# CanNode.net
KiCad netlist of a schematic drawn in Altium Designer
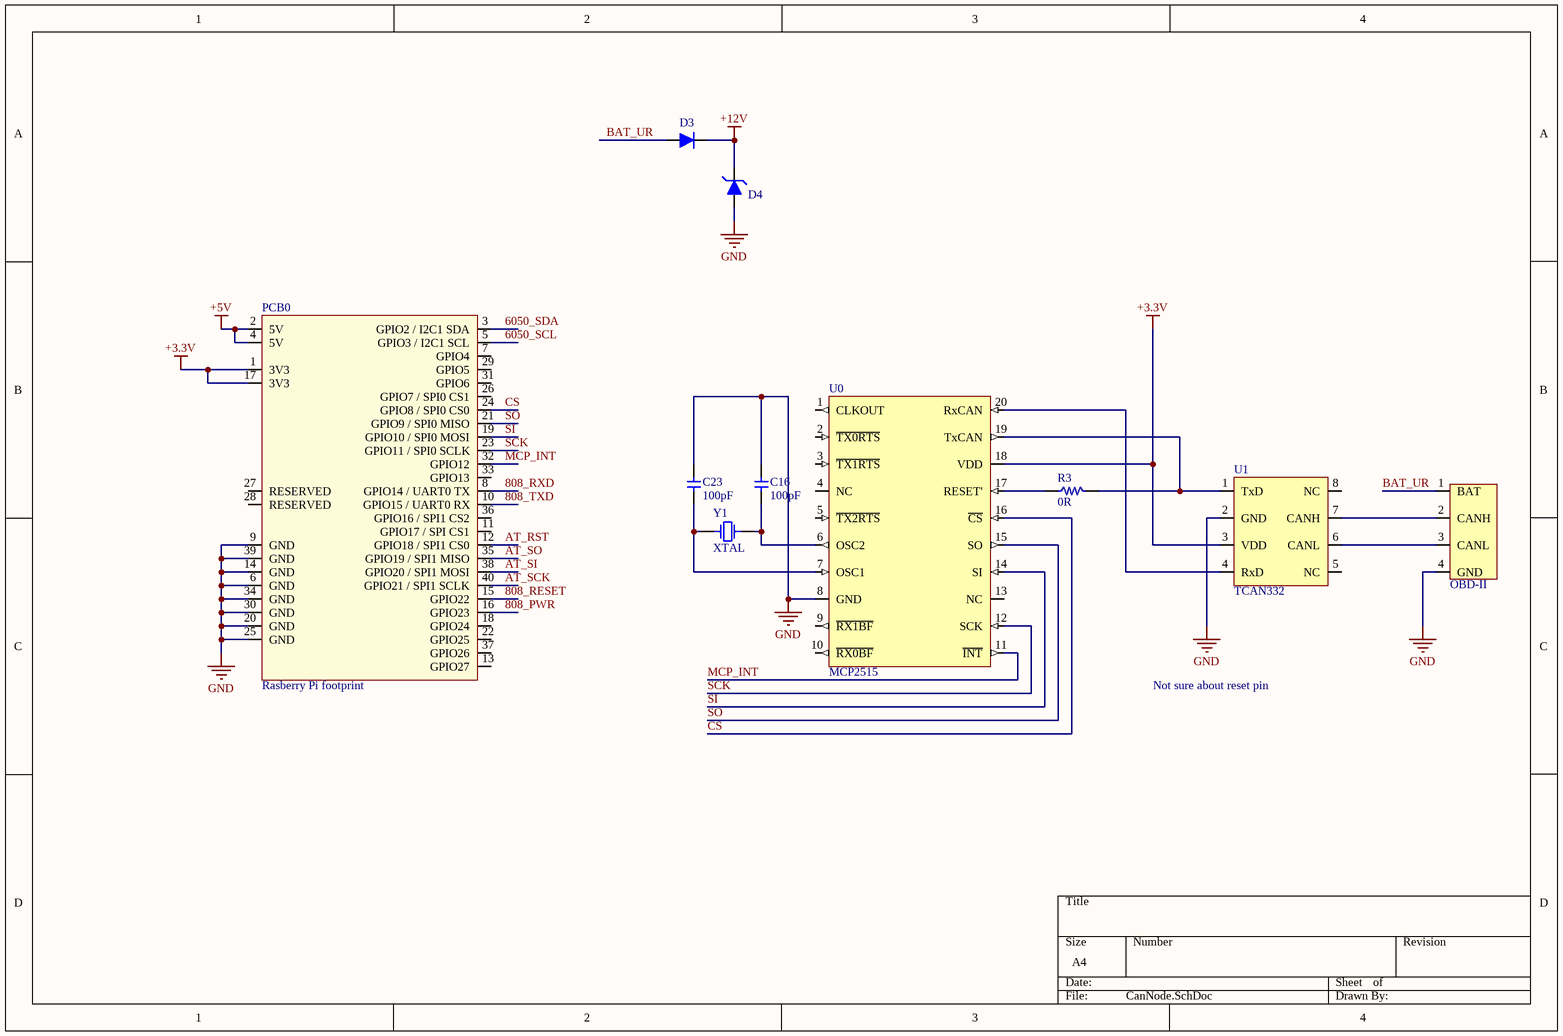
[diagram p0: CanNode.SchDoc]

(export (version "E")
  (design (tool "Eeschema 10.0.6"))
  (components
    (comp (ref "C16")
      (value "100pF")
      (footprint "0805")
      (description "Generic capacitor")
      (fields (field (name "Comment") "Generic Capacitor"))
      (libsource (lib "PowerCircuit") (part "Capacitor"))
    )
    (comp (ref "C23")
      (value "100pF")
      (footprint "0805")
      (description "Generic capacitor")
      (fields (field (name "Comment") "Generic Capacitor"))
      (libsource (lib "PowerCircuit") (part "Capacitor"))
    )
    (comp (ref "D3")
      (value "RSX301L-30TE25")
      (footprint "SMA_diode")
      (description "DIODE SCHOTTKY 30V 3A")
      (libsource (lib "PowerCircuit") (part "RSX301L-30TE25"))
    )
    (comp (ref "D4")
      (value "TVS Diode")
      (footprint "TVS Diode 15")
      (description "TVS DIODE 15VWM 24VC DO214AA")
      (fields
        (field (name "MANUFACTURER") "Vishay Semiconductor Diodes Division")
        (field (name "MANUFACTURER PART NUMBER") "SMBJ15D-M3/H")
      )
      (libsource (lib "CanNode") (part "SMBJ15D-M3/H"))
    )
    (comp (ref "OBD-II") (value "OBD-II") (footprint "OBD_II") (libsource (lib "CanNode") (part "OBD-II")))
    (comp (ref "PCB0")
      (value "Rasberry Pi footprint")
      (footprint "Rasberry PI")
      (libsource (lib "CanNode") (part "Rasberry Pi"))
    )
    (comp (ref "R3")
      (value "0R")
      (footprint "0805")
      (description "Generic Resistor")
      (fields (field (name "Comment") "Resistor"))
      (libsource (lib "PowerCircuit") (part "Resistor"))
    )
    (comp (ref "U0")
      (value "MCP2515")
      (footprint "MCP2515")
      (description "IC CAN CTLR W/SPI 2.0B 20-QFN")
      (fields
        (field (name "DIGI-KEY PART NUMBER") "MCP2515T-I/MLCT-ND")
        (field (name "NOTES") "Not sure about reset pin")
      )
      (libsource (lib "CanNode") (part "MCP2515"))
    )
    (comp (ref "U1")
      (value "TCAN332")
      (footprint "SOIC-8")
      (description "IC TXRX CAN 8SOIC")
      (fields (field (name "DIGI-KEY PART NUMBER") "296-43711-1-ND"))
      (libsource (lib "CanNode") (part "TCAN332"))
    )
    (comp (ref "Y1")
      (value "XTAL")
      (footprint "XTAL-16.000")
      (description "XTAL16.0000MHZ 18PF SMD")
      (fields
        (field (name "MANUFACTURER") "Abracon LLC")
        (field (name "MANUFACTURER PART NUMBER") "ABM7-16.000MHZ-D2Y-T")
      )
      (libsource (lib "CanNode") (part "XTAL-16.000"))
    )
  )
  (nets
    (net (code "1") (name "+3.3V") (class "Default")
      (node (ref "PCB0") (pin "1") (pinfunction "3V3_1") (pintype "passive"))
      (node (ref "PCB0") (pin "17") (pinfunction "3V3_17") (pintype "passive"))
      (node (ref "U0") (pin "18") (pinfunction "VDD_18") (pintype "power_in"))
      (node (ref "U1") (pin "3") (pinfunction "VDD_3") (pintype "passive"))
    )
    (net (code "2") (name "+5V") (class "Default")
      (node (ref "PCB0") (pin "2") (pinfunction "5V_2") (pintype "passive"))
      (node (ref "PCB0") (pin "4") (pinfunction "5V_4") (pintype "passive"))
    )
    (net (code "3") (name "+12V") (class "Default")
      (node (ref "D3") (pin "2") (pinfunction "2_2") (pintype "passive"))
      (node (ref "D4") (pin "2") (pinfunction "2_2") (pintype "passive"))
    )
    (net (code "4") (name "/808_PWR") (class "Default")
      (node (ref "PCB0") (pin "16") (pinfunction "GPIO23_16") (pintype "passive"))
    )
    (net (code "5") (name "/808_RESET") (class "Default")
      (node (ref "PCB0") (pin "15") (pinfunction "GPIO22_15") (pintype "passive"))
    )
    (net (code "6") (name "/808_RXD") (class "Default")
      (node (ref "PCB0") (pin "8") (pinfunction "GPIO14_/_UART0_TX_8") (pintype "passive"))
    )
    (net (code "7") (name "/808_TXD") (class "Default")
      (node (ref "PCB0") (pin "10") (pinfunction "GPIO15_/_UART0_RX_10") (pintype "passive"))
    )
    (net (code "8") (name "/6050_SCL") (class "Default")
      (node (ref "PCB0") (pin "5") (pinfunction "GPIO3_/_I2C1_SCL_5") (pintype "passive"))
    )
    (net (code "9") (name "/6050_SDA") (class "Default")
      (node (ref "PCB0") (pin "3") (pinfunction "GPIO2_/_I2C1_SDA_3") (pintype "passive"))
    )
    (net (code "10") (name "/AT_RST") (class "Default")
      (node (ref "PCB0") (pin "12") (pinfunction "GPIO18_/_SPI1_CS0_12") (pintype "passive"))
    )
    (net (code "11") (name "/AT_SCK") (class "Default")
      (node (ref "PCB0") (pin "40") (pinfunction "GPIO21_/_SPI1_SCLK_40") (pintype "passive"))
    )
    (net (code "12") (name "/AT_SI") (class "Default")
      (node (ref "PCB0") (pin "38") (pinfunction "GPIO20_/_SPI1_MOSI_38") (pintype "passive"))
    )
    (net (code "13") (name "/AT_SO") (class "Default")
      (node (ref "PCB0") (pin "35") (pinfunction "GPIO19_/_SPI1_MISO_35") (pintype "passive"))
    )
    (net (code "14") (name "/BAT_UR") (class "Default")
      (node (ref "D3") (pin "1") (pinfunction "1_1") (pintype "passive"))
      (node (ref "OBD-II") (pin "1") (pinfunction "BAT_1") (pintype "passive"))
    )
    (net (code "15") (name "/CS") (class "Default")
      (node (ref "PCB0") (pin "24") (pinfunction "GPIO8_/_SPI0_CS0_24") (pintype "passive"))
      (node (ref "U0") (pin "16") (pinfunction "~{CS}_16") (pintype "input"))
    )
    (net (code "16") (name "/MCP_INT") (class "Default")
      (node (ref "PCB0") (pin "32") (pinfunction "GPIO12_32") (pintype "passive"))
      (node (ref "U0") (pin "11") (pinfunction "~{INT}_11") (pintype "output"))
    )
    (net (code "17") (name "/SCK") (class "Default")
      (node (ref "PCB0") (pin "23") (pinfunction "GPIO11_/_SPI0_SCLK_23") (pintype "passive"))
      (node (ref "U0") (pin "12") (pinfunction "SCK_12") (pintype "input"))
    )
    (net (code "18") (name "/SI") (class "Default")
      (node (ref "PCB0") (pin "19") (pinfunction "GPIO10_/_SPI0_MOSI_19") (pintype "passive"))
      (node (ref "U0") (pin "14") (pinfunction "SI_14") (pintype "input"))
    )
    (net (code "19") (name "/SO") (class "Default")
      (node (ref "PCB0") (pin "21") (pinfunction "GPIO9_/_SPI0_MISO_21") (pintype "passive"))
      (node (ref "U0") (pin "15") (pinfunction "SO_15") (pintype "output"))
    )
    (net (code "20") (name "GND") (class "Default")
      (node (ref "C16") (pin "2") (pinfunction "2_2") (pintype "passive"))
      (node (ref "C23") (pin "2") (pinfunction "2_2") (pintype "passive"))
      (node (ref "D4") (pin "1") (pinfunction "1_1") (pintype "passive"))
      (node (ref "OBD-II") (pin "4") (pinfunction "GND_4") (pintype "passive"))
      (node (ref "PCB0") (pin "14") (pinfunction "GND_14") (pintype "passive"))
      (node (ref "PCB0") (pin "20") (pinfunction "GND_20") (pintype "passive"))
      (node (ref "PCB0") (pin "25") (pinfunction "GND_25") (pintype "passive"))
      (node (ref "PCB0") (pin "30") (pinfunction "GND_30") (pintype "passive"))
      (node (ref "PCB0") (pin "34") (pinfunction "GND_34") (pintype "passive"))
      (node (ref "PCB0") (pin "39") (pinfunction "GND_39") (pintype "passive"))
      (node (ref "PCB0") (pin "6") (pinfunction "GND_6") (pintype "passive"))
      (node (ref "PCB0") (pin "9") (pinfunction "GND_9") (pintype "passive"))
      (node (ref "U0") (pin "8") (pinfunction "GND_8") (pintype "power_in"))
      (node (ref "U1") (pin "2") (pinfunction "GND_2") (pintype "passive"))
    )
    (net (code "21") (name "Net-(OBD-II-CANH)") (class "Default")
      (node (ref "OBD-II") (pin "2") (pinfunction "CANH_2") (pintype "passive"))
      (node (ref "U1") (pin "7") (pinfunction "CANH_7") (pintype "passive"))
    )
    (net (code "22") (name "Net-(OBD-II-CANL)") (class "Default")
      (node (ref "OBD-II") (pin "3") (pinfunction "CANL_3") (pintype "passive"))
      (node (ref "U1") (pin "6") (pinfunction "CANL_6") (pintype "passive"))
    )
    (net (code "23") (name "Net-(U0-OSC1)") (class "Default")
      (node (ref "C23") (pin "1") (pinfunction "1_1") (pintype "passive"))
      (node (ref "U0") (pin "7") (pinfunction "OSC1_7") (pintype "input"))
      (node (ref "Y1") (pin "0") (pinfunction "0_0") (pintype "passive"))
    )
    (net (code "24") (name "Net-(U0-OSC2)") (class "Default")
      (node (ref "C16") (pin "1") (pinfunction "1_1") (pintype "passive"))
      (node (ref "U0") (pin "6") (pinfunction "OSC2_6") (pintype "output"))
      (node (ref "Y1") (pin "1") (pinfunction "1_1") (pintype "passive"))
    )
    (net (code "25") (name "Net-(U0-RESET')") (class "Default")
      (node (ref "R3") (pin "1") (pinfunction "1_1") (pintype "passive"))
      (node (ref "U0") (pin "17") (pinfunction "RESET'_17") (pintype "input"))
    )
    (net (code "26") (name "Net-(U0-RxCAN)") (class "Default")
      (node (ref "U0") (pin "20") (pinfunction "RxCAN_20") (pintype "input"))
      (node (ref "U1") (pin "4") (pinfunction "RxD_4") (pintype "passive"))
    )
    (net (code "27") (name "Net-(U0-TxCAN)") (class "Default")
      (node (ref "R3") (pin "2") (pinfunction "2_2") (pintype "passive"))
      (node (ref "U0") (pin "19") (pinfunction "TxCAN_19") (pintype "output"))
      (node (ref "U1") (pin "1") (pinfunction "TxD_1") (pintype "passive"))
    )
    (net (code "28") (name "unconnected-(PCB0-GPIO4-Pad7)") (class "Default")
      (node (ref "PCB0") (pin "7") (pinfunction "GPIO4_7") (pintype "passive"))
    )
    (net (code "29") (name "unconnected-(PCB0-GPIO5-Pad29)") (class "Default")
      (node (ref "PCB0") (pin "29") (pinfunction "GPIO5_29") (pintype "passive"))
    )
    (net (code "30") (name "unconnected-(PCB0-GPIO6-Pad31)") (class "Default")
      (node (ref "PCB0") (pin "31") (pinfunction "GPIO6_31") (pintype "passive"))
    )
    (net (code "31") (name "unconnected-(PCB0-GPIO7_{slash}_SPI0_CS1-Pad26)") (class "Default")
      (node (ref "PCB0") (pin "26") (pinfunction "GPIO7_/_SPI0_CS1_26") (pintype "passive"))
    )
    (net (code "32") (name "unconnected-(PCB0-GPIO13-Pad33)") (class "Default")
      (node (ref "PCB0") (pin "33") (pinfunction "GPIO13_33") (pintype "passive"))
    )
    (net (code "33") (name "unconnected-(PCB0-GPIO16_{slash}_SPI1_CS2-Pad36)") (class "Default")
      (node (ref "PCB0") (pin "36") (pinfunction "GPIO16_/_SPI1_CS2_36") (pintype "passive"))
    )
    (net (code "34") (name "unconnected-(PCB0-GPIO17_{slash}_SPI_CS1-Pad11)") (class "Default")
      (node (ref "PCB0") (pin "11") (pinfunction "GPIO17_/_SPI_CS1_11") (pintype "passive"))
    )
    (net (code "35") (name "unconnected-(PCB0-GPIO24-Pad18)") (class "Default")
      (node (ref "PCB0") (pin "18") (pinfunction "GPIO24_18") (pintype "passive"))
    )
    (net (code "36") (name "unconnected-(PCB0-GPIO25-Pad22)") (class "Default")
      (node (ref "PCB0") (pin "22") (pinfunction "GPIO25_22") (pintype "passive"))
    )
    (net (code "37") (name "unconnected-(PCB0-GPIO26-Pad37)") (class "Default")
      (node (ref "PCB0") (pin "37") (pinfunction "GPIO26_37") (pintype "passive"))
    )
    (net (code "38") (name "unconnected-(PCB0-GPIO27-Pad13)") (class "Default")
      (node (ref "PCB0") (pin "13") (pinfunction "GPIO27_13") (pintype "passive"))
    )
    (net (code "39") (name "unconnected-(PCB0-RESERVED-Pad27)") (class "Default")
      (node (ref "PCB0") (pin "27") (pinfunction "RESERVED_27") (pintype "passive"))
    )
    (net (code "40") (name "unconnected-(PCB0-RESERVED-Pad28)") (class "Default")
      (node (ref "PCB0") (pin "28") (pinfunction "RESERVED_28") (pintype "passive"))
    )
    (net (code "41") (name "unconnected-(U0-CLKOUT-Pad1)") (class "Default")
      (node (ref "U0") (pin "1") (pinfunction "CLKOUT_1") (pintype "output"))
    )
    (net (code "42") (name "unconnected-(U0-NC-Pad4)") (class "Default")
      (node (ref "U0") (pin "4") (pinfunction "NC_4") (pintype "passive"))
    )
    (net (code "43") (name "unconnected-(U0-NC-Pad13)") (class "Default")
      (node (ref "U0") (pin "13") (pinfunction "NC_13") (pintype "passive"))
    )
    (net (code "44") (name "unconnected-(U0-~{RX0BF}-Pad10)") (class "Default")
      (node (ref "U0") (pin "10") (pinfunction "~{RX0BF}_10") (pintype "output"))
    )
    (net (code "45") (name "unconnected-(U0-~{RX1BF}-Pad9)") (class "Default")
      (node (ref "U0") (pin "9") (pinfunction "~{RX1BF}_9") (pintype "output"))
    )
    (net (code "46") (name "unconnected-(U0-~{TX0RTS}-Pad2)") (class "Default")
      (node (ref "U0") (pin "2") (pinfunction "~{TX0RTS}_2") (pintype "input"))
    )
    (net (code "47") (name "unconnected-(U0-~{TX1RTS}-Pad3)") (class "Default")
      (node (ref "U0") (pin "3") (pinfunction "~{TX1RTS}_3") (pintype "input"))
    )
    (net (code "48") (name "unconnected-(U0-~{TX2RTS}-Pad5)") (class "Default")
      (node (ref "U0") (pin "5") (pinfunction "~{TX2RTS}_5") (pintype "input"))
    )
    (net (code "49") (name "unconnected-(U1-NC-Pad5)") (class "Default")
      (node (ref "U1") (pin "5") (pinfunction "NC_5") (pintype "passive"))
    )
    (net (code "50") (name "unconnected-(U1-NC-Pad8)") (class "Default")
      (node (ref "U1") (pin "8") (pinfunction "NC_8") (pintype "passive"))
    )
  )
)
